# Tracksoar_imu_shield.net
KiCad netlist of a schematic drawn in EAGLE
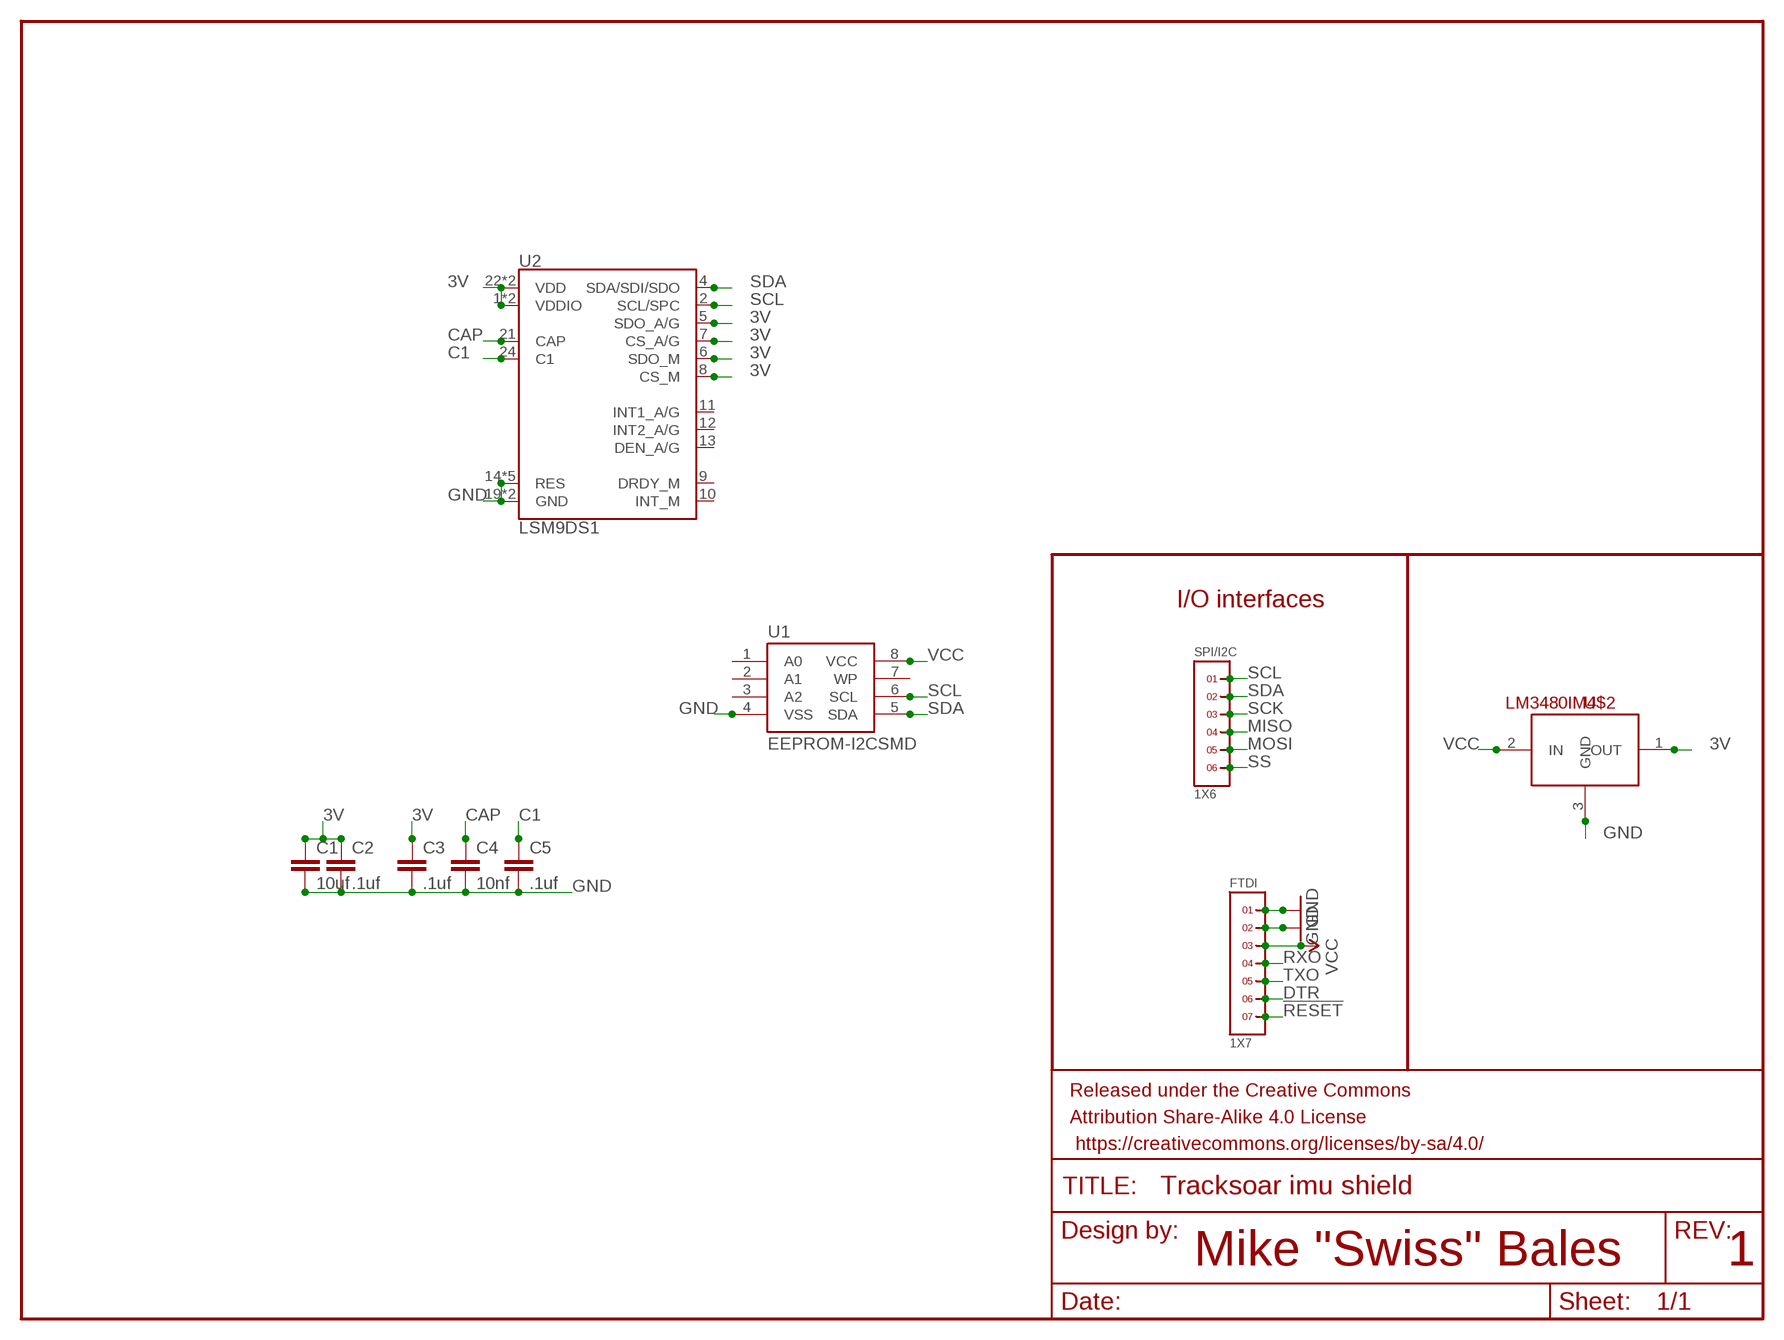
[diagram p0: schematic, sheet 1]

(export (version "E")
  (design (tool "Eeschema 10.0.6"))
  (components
    (comp (ref "C1")
      (value "10uf")
      (footprint "eagle-import:0805")
      (libsource (lib "eagle-import") (part "CAP0805"))
    )
    (comp (ref "C2")
      (value ".1uf")
      (footprint "eagle-import:0805")
      (libsource (lib "eagle-import") (part "CAP0805"))
    )
    (comp (ref "C3")
      (value ".1uf")
      (footprint "eagle-import:0805")
      (libsource (lib "eagle-import") (part "CAP0805"))
    )
    (comp (ref "C4")
      (value "10nf")
      (footprint "eagle-import:0805")
      (libsource (lib "eagle-import") (part "CAP0805"))
    )
    (comp (ref "C5")
      (value ".1uf")
      (footprint "eagle-import:0805")
      (libsource (lib "eagle-import") (part "CAP0805"))
    )
    (comp (ref "FRAME1")
      (value "FRAME-LETTER")
      (footprint "eagle-import:CREATIVE_COMMONS")
      (libsource (lib "eagle-import") (part "FRAME-LETTER"))
    )
    (comp (ref "FTDI")
      (value "1X7")
      (footprint "eagle-import:1X7")
      (libsource (lib "eagle-import") (part "1X7"))
    )
    (comp (ref "SPI/I2C")
      (value "1X6")
      (footprint "eagle-import:1X6")
      (libsource (lib "eagle-import") (part "1X6"))
    )
    (comp (ref "U$2")
      (value "LM3480IM4")
      (footprint "eagle-import:SOT23-3")
      (libsource (lib "eagle-import") (part "LM3480IM4"))
    )
    (comp (ref "U1")
      (value "EEPROM-I2CSMD")
      (footprint "eagle-import:SO08")
      (libsource (lib "eagle-import") (part "EEPROM-I2CSMD"))
    )
    (comp (ref "U2")
      (value "LSM9DS1")
      (footprint "eagle-import:LGA24-8X4")
      (libsource (lib "eagle-import") (part "LSM9DS1"))
    )
  )
  (nets
    (net (code "1") (name "/3V") (class "Default")
      (node (ref "C1") (pin "1") (pinfunction "1_1") (pintype "passive"))
      (node (ref "C2") (pin "1") (pinfunction "1_1") (pintype "passive"))
      (node (ref "C3") (pin "1") (pinfunction "1_1") (pintype "passive"))
      (node (ref "U$2") (pin "1") (pinfunction "OUT_1") (pintype "bidirectional"))
      (node (ref "U2") (pin "1") (pinfunction "VDDIO_1") (pintype "bidirectional"))
      (node (ref "U2") (pin "22") (pinfunction "VDD_22") (pintype "bidirectional"))
      (node (ref "U2") (pin "23") (pinfunction "VDD_23") (pintype "bidirectional"))
      (node (ref "U2") (pin "3") (pinfunction "VDDIO_3") (pintype "bidirectional"))
      (node (ref "U2") (pin "5") (pinfunction "SDO_A/G_5") (pintype "bidirectional"))
      (node (ref "U2") (pin "6") (pinfunction "SDO_M_6") (pintype "bidirectional"))
      (node (ref "U2") (pin "7") (pinfunction "CS_A/G_7") (pintype "bidirectional"))
      (node (ref "U2") (pin "8") (pinfunction "CS_M_8") (pintype "bidirectional"))
    )
    (net (code "2") (name "/C1") (class "Default")
      (node (ref "C5") (pin "1") (pinfunction "1_1") (pintype "passive"))
      (node (ref "U2") (pin "24") (pinfunction "C1_24") (pintype "bidirectional"))
    )
    (net (code "3") (name "/CAP") (class "Default")
      (node (ref "C4") (pin "1") (pinfunction "1_1") (pintype "passive"))
      (node (ref "U2") (pin "21") (pinfunction "CAP_21") (pintype "bidirectional"))
    )
    (net (code "4") (name "/DTR") (class "Default")
      (node (ref "FTDI") (pin "6") (pinfunction "6_6") (pintype "bidirectional"))
    )
    (net (code "5") (name "/MISO") (class "Default")
      (node (ref "SPI/I2C") (pin "4") (pinfunction "4_4") (pintype "bidirectional"))
    )
    (net (code "6") (name "/MOSI") (class "Default")
      (node (ref "SPI/I2C") (pin "5") (pinfunction "5_5") (pintype "bidirectional"))
    )
    (net (code "7") (name "/RXO") (class "Default")
      (node (ref "FTDI") (pin "4") (pinfunction "4_4") (pintype "bidirectional"))
    )
    (net (code "8") (name "/SCK") (class "Default")
      (node (ref "SPI/I2C") (pin "3") (pinfunction "3_3") (pintype "bidirectional"))
    )
    (net (code "9") (name "/SCL") (class "Default")
      (node (ref "SPI/I2C") (pin "1") (pinfunction "1_1") (pintype "bidirectional"))
      (node (ref "U1") (pin "6") (pinfunction "SCL_6") (pintype "bidirectional"))
      (node (ref "U2") (pin "2") (pinfunction "SCL/SPC_2") (pintype "bidirectional"))
    )
    (net (code "10") (name "/SDA") (class "Default")
      (node (ref "SPI/I2C") (pin "2") (pinfunction "2_2") (pintype "bidirectional"))
      (node (ref "U1") (pin "5") (pinfunction "SDA_5") (pintype "bidirectional"))
      (node (ref "U2") (pin "4") (pinfunction "SDA/SDI/SDO_4") (pintype "bidirectional"))
    )
    (net (code "11") (name "/SS") (class "Default")
      (node (ref "SPI/I2C") (pin "6") (pinfunction "6_6") (pintype "bidirectional"))
    )
    (net (code "12") (name "/TXO") (class "Default")
      (node (ref "FTDI") (pin "5") (pinfunction "5_5") (pintype "bidirectional"))
    )
    (net (code "13") (name "/~{RESET}") (class "Default")
      (node (ref "FTDI") (pin "7") (pinfunction "7_7") (pintype "bidirectional"))
    )
    (net (code "14") (name "GND") (class "Default")
      (node (ref "C1") (pin "2") (pinfunction "2_2") (pintype "passive"))
      (node (ref "C2") (pin "2") (pinfunction "2_2") (pintype "passive"))
      (node (ref "C3") (pin "2") (pinfunction "2_2") (pintype "passive"))
      (node (ref "C4") (pin "2") (pinfunction "2_2") (pintype "passive"))
      (node (ref "C5") (pin "2") (pinfunction "2_2") (pintype "passive"))
      (node (ref "FTDI") (pin "1") (pinfunction "1_1") (pintype "bidirectional"))
      (node (ref "FTDI") (pin "2") (pinfunction "2_2") (pintype "bidirectional"))
      (node (ref "U$2") (pin "3") (pinfunction "GND_3") (pintype "bidirectional"))
      (node (ref "U1") (pin "4") (pinfunction "VSS_4") (pintype "power_in"))
      (node (ref "U2") (pin "14") (pinfunction "RES_14") (pintype "bidirectional"))
      (node (ref "U2") (pin "15") (pinfunction "RES_15") (pintype "bidirectional"))
      (node (ref "U2") (pin "16") (pinfunction "RES_16") (pintype "bidirectional"))
      (node (ref "U2") (pin "17") (pinfunction "RES_17") (pintype "bidirectional"))
      (node (ref "U2") (pin "18") (pinfunction "RES_18") (pintype "bidirectional"))
      (node (ref "U2") (pin "19") (pinfunction "GND_19") (pintype "bidirectional"))
      (node (ref "U2") (pin "20") (pinfunction "GND_20") (pintype "bidirectional"))
    )
    (net (code "15") (name "VCC") (class "Default")
      (node (ref "FTDI") (pin "3") (pinfunction "3_3") (pintype "bidirectional"))
      (node (ref "U$2") (pin "2") (pinfunction "IN_2") (pintype "bidirectional"))
      (node (ref "U1") (pin "8") (pinfunction "VCC_8") (pintype "power_in"))
    )
    (net (code "16") (name "unconnected-(U1-A0-Pad1)") (class "Default")
      (node (ref "U1") (pin "1") (pinfunction "A0_1") (pintype "bidirectional"))
    )
    (net (code "17") (name "unconnected-(U1-A1-Pad2)") (class "Default")
      (node (ref "U1") (pin "2") (pinfunction "A1_2") (pintype "bidirectional"))
    )
    (net (code "18") (name "unconnected-(U1-A2-Pad3)") (class "Default")
      (node (ref "U1") (pin "3") (pinfunction "A2_3") (pintype "bidirectional"))
    )
    (net (code "19") (name "unconnected-(U1-WP-Pad7)") (class "Default")
      (node (ref "U1") (pin "7") (pinfunction "WP_7") (pintype "bidirectional"))
    )
    (net (code "20") (name "unconnected-(U2-DEN_A{slash}G-Pad13)") (class "Default")
      (node (ref "U2") (pin "13") (pinfunction "DEN_A/G_13") (pintype "bidirectional"))
    )
    (net (code "21") (name "unconnected-(U2-DRDY_M-Pad9)") (class "Default")
      (node (ref "U2") (pin "9") (pinfunction "DRDY_M_9") (pintype "bidirectional"))
    )
    (net (code "22") (name "unconnected-(U2-INT1_A{slash}G-Pad11)") (class "Default")
      (node (ref "U2") (pin "11") (pinfunction "INT1_A/G_11") (pintype "bidirectional"))
    )
    (net (code "23") (name "unconnected-(U2-INT2_A{slash}G-Pad12)") (class "Default")
      (node (ref "U2") (pin "12") (pinfunction "INT2_A/G_12") (pintype "bidirectional"))
    )
    (net (code "24") (name "unconnected-(U2-INT_M-Pad10)") (class "Default")
      (node (ref "U2") (pin "10") (pinfunction "INT_M_10") (pintype "bidirectional"))
    )
  )
)
